# Audio_Output_Line_Out.net
KiCad netlist of a schematic drawn in Altium Designer
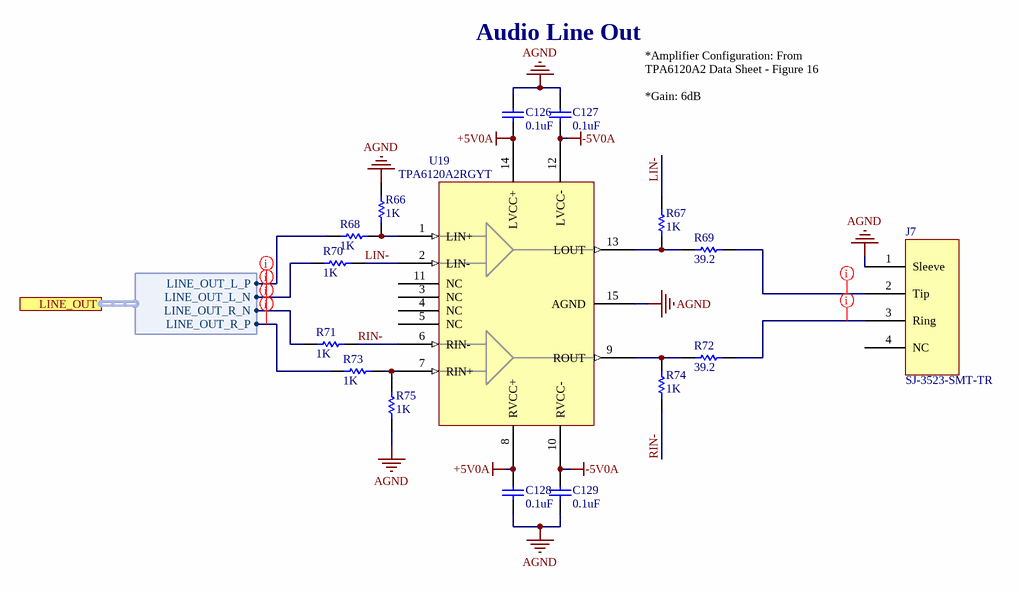
[diagram p0: Audio_Output_Line_Out.SchDoc]

(export (version "E")
  (design (tool "Eeschema 10.0.6"))
  (components
    (comp (ref "C126")
      (value "CL10F104ZO8NNNC")
      (footprint "3-0603_L")
      (description "CAP CER 0.1UF 16V Y5V 0603")
      (fields
        (field (name "MANUFACTURER") "Samsung")
        (field (name "TOLERANCE") "80%")
        (field (name "CAPACITANCE") "0.1uF")
      )
      (libsource (lib "Schematic_Components_CD") (part "CL10F104ZO8NNNC"))
    )
    (comp (ref "C127")
      (value "CL10F104ZO8NNNC")
      (footprint "3-0603_L")
      (description "CAP CER 0.1UF 16V Y5V 0603")
      (fields
        (field (name "MANUFACTURER") "Samsung")
        (field (name "TOLERANCE") "80%")
        (field (name "CAPACITANCE") "0.1uF")
      )
      (libsource (lib "Schematic_Components_CD") (part "CL10F104ZO8NNNC"))
    )
    (comp (ref "C128")
      (value "CL10F104ZO8NNNC")
      (footprint "3-0603_L")
      (description "CAP CER 0.1UF 16V Y5V 0603")
      (fields
        (field (name "MANUFACTURER") "Samsung")
        (field (name "TOLERANCE") "80%")
        (field (name "CAPACITANCE") "0.1uF")
      )
      (libsource (lib "Schematic_Components_CD") (part "CL10F104ZO8NNNC"))
    )
    (comp (ref "C129")
      (value "CL10F104ZO8NNNC")
      (footprint "3-0603_L")
      (description "CAP CER 0.1UF 16V Y5V 0603")
      (fields
        (field (name "MANUFACTURER") "Samsung")
        (field (name "TOLERANCE") "80%")
        (field (name "CAPACITANCE") "0.1uF")
      )
      (libsource (lib "Schematic_Components_CD") (part "CL10F104ZO8NNNC"))
    )
    (comp (ref "J7")
      (value "SJ-3523-SMT-TR")
      (footprint "SJ-3523-SMT-TR")
      (description "3.50mm (0.141\", 1/8\", Mini Plug) - Headphone Phone Jack Stereo Connector Solder")
      (fields
        (field (name "MANUFACTURER") "CUI Inc.")
        (field (name "MANUFACTURER PART NUMBER") "SJ-3523-SMT-TR")
        (field (name "PUBLISHER") "Altium Limited")
      )
      (libsource (lib "NIH_DE0_Nano_Daughter_Card_Library") (part "SJ-3523-SMT-TR"))
    )
    (comp (ref "R66")
      (value "ERJ-3EKF1001V")
      (footprint "3-0603_R_L")
      (description "RES 1.00K OHM 1/10W 1% 0603 SMD")
      (fields
        (field (name "MANUFACTURER") "Panasonic - ECG")
        (field (name "TOLERANCE") "±1%")
        (field (name "RESISTANCE (OHMS)") "1K")
      )
      (libsource (lib "Schematic_Components") (part "ERJ-3EKF1001V"))
    )
    (comp (ref "R67")
      (value "ERJ-3EKF1001V")
      (footprint "3-0603_R_L")
      (description "RES 1.00K OHM 1/10W 1% 0603 SMD")
      (fields
        (field (name "MANUFACTURER") "Panasonic - ECG")
        (field (name "TOLERANCE") "±1%")
        (field (name "RESISTANCE (OHMS)") "1K")
      )
      (libsource (lib "Schematic_Components") (part "ERJ-3EKF1001V"))
    )
    (comp (ref "R68")
      (value "ERJ-3EKF1001V")
      (footprint "3-0603_R_L")
      (description "RES 1.00K OHM 1/10W 1% 0603 SMD")
      (fields
        (field (name "MANUFACTURER") "Panasonic - ECG")
        (field (name "TOLERANCE") "±1%")
        (field (name "RESISTANCE (OHMS)") "1K")
      )
      (libsource (lib "Schematic_Components") (part "ERJ-3EKF1001V"))
    )
    (comp (ref "R69")
      (value "ERJ-3EKF39R2V")
      (footprint "3-0603_R_L")
      (description "n RES SMD 39.2 OHM 1% 1/10W 0603")
      (fields
        (field (name "MANUFACTURER") "Panasonic Electronic Components")
        (field (name "TOLERANCE") "±1%")
        (field (name "RESISTANCE (OHMS)") "39.2")
      )
      (libsource (lib "Schematic_Components") (part "ERJ-3EKF39R2V"))
    )
    (comp (ref "R70")
      (value "ERJ-3EKF1001V")
      (footprint "3-0603_R_L")
      (description "RES 1.00K OHM 1/10W 1% 0603 SMD")
      (fields
        (field (name "MANUFACTURER") "Panasonic - ECG")
        (field (name "TOLERANCE") "±1%")
        (field (name "RESISTANCE (OHMS)") "1K")
      )
      (libsource (lib "Schematic_Components") (part "ERJ-3EKF1001V"))
    )
    (comp (ref "R71")
      (value "ERJ-3EKF1001V")
      (footprint "3-0603_R_L")
      (description "RES 1.00K OHM 1/10W 1% 0603 SMD")
      (fields
        (field (name "MANUFACTURER") "Panasonic - ECG")
        (field (name "TOLERANCE") "±1%")
        (field (name "RESISTANCE (OHMS)") "1K")
      )
      (libsource (lib "Schematic_Components") (part "ERJ-3EKF1001V"))
    )
    (comp (ref "R72")
      (value "ERJ-3EKF39R2V")
      (footprint "3-0603_R_L")
      (description "n RES SMD 39.2 OHM 1% 1/10W 0603")
      (fields
        (field (name "MANUFACTURER") "Panasonic Electronic Components")
        (field (name "TOLERANCE") "±1%")
        (field (name "RESISTANCE (OHMS)") "39.2")
      )
      (libsource (lib "Schematic_Components") (part "ERJ-3EKF39R2V"))
    )
    (comp (ref "R73")
      (value "ERJ-3EKF1001V")
      (footprint "3-0603_R_L")
      (description "RES 1.00K OHM 1/10W 1% 0603 SMD")
      (fields
        (field (name "MANUFACTURER") "Panasonic - ECG")
        (field (name "TOLERANCE") "±1%")
        (field (name "RESISTANCE (OHMS)") "1K")
      )
      (libsource (lib "Schematic_Components") (part "ERJ-3EKF1001V"))
    )
    (comp (ref "R74")
      (value "ERJ-3EKF1001V")
      (footprint "3-0603_R_L")
      (description "RES 1.00K OHM 1/10W 1% 0603 SMD")
      (fields
        (field (name "MANUFACTURER") "Panasonic - ECG")
        (field (name "TOLERANCE") "±1%")
        (field (name "RESISTANCE (OHMS)") "1K")
      )
      (libsource (lib "Schematic_Components") (part "ERJ-3EKF1001V"))
    )
    (comp (ref "R75")
      (value "ERJ-3EKF1001V")
      (footprint "3-0603_R_L")
      (description "RES 1.00K OHM 1/10W 1% 0603 SMD")
      (fields
        (field (name "MANUFACTURER") "Panasonic - ECG")
        (field (name "TOLERANCE") "±1%")
        (field (name "RESISTANCE (OHMS)") "1K")
      )
      (libsource (lib "Schematic_Components") (part "ERJ-3EKF1001V"))
    )
    (comp (ref "U19")
      (value "TPA6120A2RGYT")
      (footprint "PQFN50P350X350X100_HS-15N")
      (description "Amplifier IC Headphones, 2-Channel (Stereo) Class AB 14-VQFN (3.5x3.5)")
      (fields
        (field (name "MANUFACTURER") "Texas Instruments")
        (field (name "MANUFACTURER PART NUMBER") "TPA6120A2RGYT")
        (field (name "PUBLISHER") "Altium Limited")
      )
      (libsource (lib "Schematic_Components_CD") (part "TPA6120A2RGYT"))
    )
  )
  (nets
    (net (code "2") (name "+5V0A") (class "Default")
      (node (ref "C126") (pin "2") (pinfunction "2_2") (pintype "passive"))
      (node (ref "C128") (pin "1") (pinfunction "1_1") (pintype "passive"))
      (node (ref "U19") (pin "14") (pinfunction "LVCC+_14") (pintype "passive"))
      (node (ref "U19") (pin "8") (pinfunction "RVCC+_8") (pintype "passive"))
    )
    (net (code "3") (name "-5V0A") (class "Default")
      (node (ref "C127") (pin "2") (pinfunction "2_2") (pintype "passive"))
      (node (ref "C129") (pin "1") (pinfunction "1_1") (pintype "passive"))
      (node (ref "U19") (pin "10") (pinfunction "RVCC-_10") (pintype "passive"))
      (node (ref "U19") (pin "12") (pinfunction "LVCC-_12") (pintype "passive"))
    )
    (net (code "4") (name "/LIN-") (class "Default")
      (node (ref "R67") (pin "1") (pinfunction "1_1") (pintype "passive"))
      (node (ref "R70") (pin "2") (pinfunction "2_2") (pintype "passive"))
      (node (ref "U19") (pin "2") (pinfunction "LIN-_2") (pintype "input"))
    )
    (net (code "5") (name "/LINE_OUT_L_N") (class "Default")
      (node (ref "R70") (pin "1") (pinfunction "1_1") (pintype "passive"))
    )
    (net (code "6") (name "/LINE_OUT_L_P") (class "Default")
      (node (ref "R68") (pin "1") (pinfunction "1_1") (pintype "passive"))
    )
    (net (code "7") (name "/LINE_OUT_R_N") (class "Default")
      (node (ref "R71") (pin "1") (pinfunction "1_1") (pintype "passive"))
    )
    (net (code "8") (name "/LINE_OUT_R_P") (class "Default")
      (node (ref "R73") (pin "1") (pinfunction "1_1") (pintype "passive"))
    )
    (net (code "9") (name "/RIN-") (class "Default")
      (node (ref "R71") (pin "2") (pinfunction "2_2") (pintype "passive"))
      (node (ref "R74") (pin "2") (pinfunction "2_2") (pintype "passive"))
      (node (ref "U19") (pin "6") (pinfunction "RIN-_6") (pintype "input"))
    )
    (net (code "11") (name "AGND") (class "Default")
      (node (ref "C126") (pin "1") (pinfunction "1_1") (pintype "passive"))
      (node (ref "C127") (pin "1") (pinfunction "1_1") (pintype "passive"))
      (node (ref "C128") (pin "2") (pinfunction "2_2") (pintype "passive"))
      (node (ref "C129") (pin "2") (pinfunction "2_2") (pintype "passive"))
      (node (ref "J7") (pin "1") (pinfunction "Sleeve_1") (pintype "passive"))
      (node (ref "R66") (pin "2") (pinfunction "2_2") (pintype "passive"))
      (node (ref "R75") (pin "1") (pinfunction "1_1") (pintype "passive"))
      (node (ref "U19") (pin "15") (pinfunction "AGND_15") (pintype "passive"))
    )
    (net (code "12") (name "Net-(J7-Ring)") (class "Default")
      (node (ref "J7") (pin "3") (pinfunction "Ring_3") (pintype "passive"))
      (node (ref "R72") (pin "2") (pinfunction "2_2") (pintype "passive"))
    )
    (net (code "13") (name "Net-(J7-Tip)") (class "Default")
      (node (ref "J7") (pin "2") (pinfunction "Tip_2") (pintype "passive"))
      (node (ref "R69") (pin "2") (pinfunction "2_2") (pintype "passive"))
    )
    (net (code "14") (name "Net-(U19-LIN+)") (class "Default")
      (node (ref "R66") (pin "1") (pinfunction "1_1") (pintype "passive"))
      (node (ref "R68") (pin "2") (pinfunction "2_2") (pintype "passive"))
      (node (ref "U19") (pin "1") (pinfunction "LIN+_1") (pintype "input"))
    )
    (net (code "15") (name "Net-(U19-LOUT)") (class "Default")
      (node (ref "R67") (pin "2") (pinfunction "2_2") (pintype "passive"))
      (node (ref "R69") (pin "1") (pinfunction "1_1") (pintype "passive"))
      (node (ref "U19") (pin "13") (pinfunction "LOUT_13") (pintype "output"))
    )
    (net (code "16") (name "Net-(U19-RIN+)") (class "Default")
      (node (ref "R73") (pin "2") (pinfunction "2_2") (pintype "passive"))
      (node (ref "R75") (pin "2") (pinfunction "2_2") (pintype "passive"))
      (node (ref "U19") (pin "7") (pinfunction "RIN+_7") (pintype "input"))
    )
    (net (code "17") (name "Net-(U19-ROUT)") (class "Default")
      (node (ref "R72") (pin "1") (pinfunction "1_1") (pintype "passive"))
      (node (ref "R74") (pin "1") (pinfunction "1_1") (pintype "passive"))
      (node (ref "U19") (pin "9") (pinfunction "ROUT_9") (pintype "output"))
    )
    (net (code "18") (name "unconnected-(J7-NC-Pad4)") (class "Default")
      (node (ref "J7") (pin "4") (pinfunction "NC_4") (pintype "passive"))
    )
    (net (code "19") (name "unconnected-(U19-NC-Pad3)") (class "Default")
      (node (ref "U19") (pin "3") (pinfunction "NC_3") (pintype "passive"))
    )
    (net (code "20") (name "unconnected-(U19-NC-Pad4)") (class "Default")
      (node (ref "U19") (pin "4") (pinfunction "NC_4") (pintype "passive"))
    )
    (net (code "21") (name "unconnected-(U19-NC-Pad5)") (class "Default")
      (node (ref "U19") (pin "5") (pinfunction "NC_5") (pintype "passive"))
    )
    (net (code "22") (name "unconnected-(U19-NC-Pad11)") (class "Default")
      (node (ref "U19") (pin "11") (pinfunction "NC_11") (pintype "passive"))
    )
  )
)
